# changer.net
KiCad netlist of a schematic drawn in EAGLE
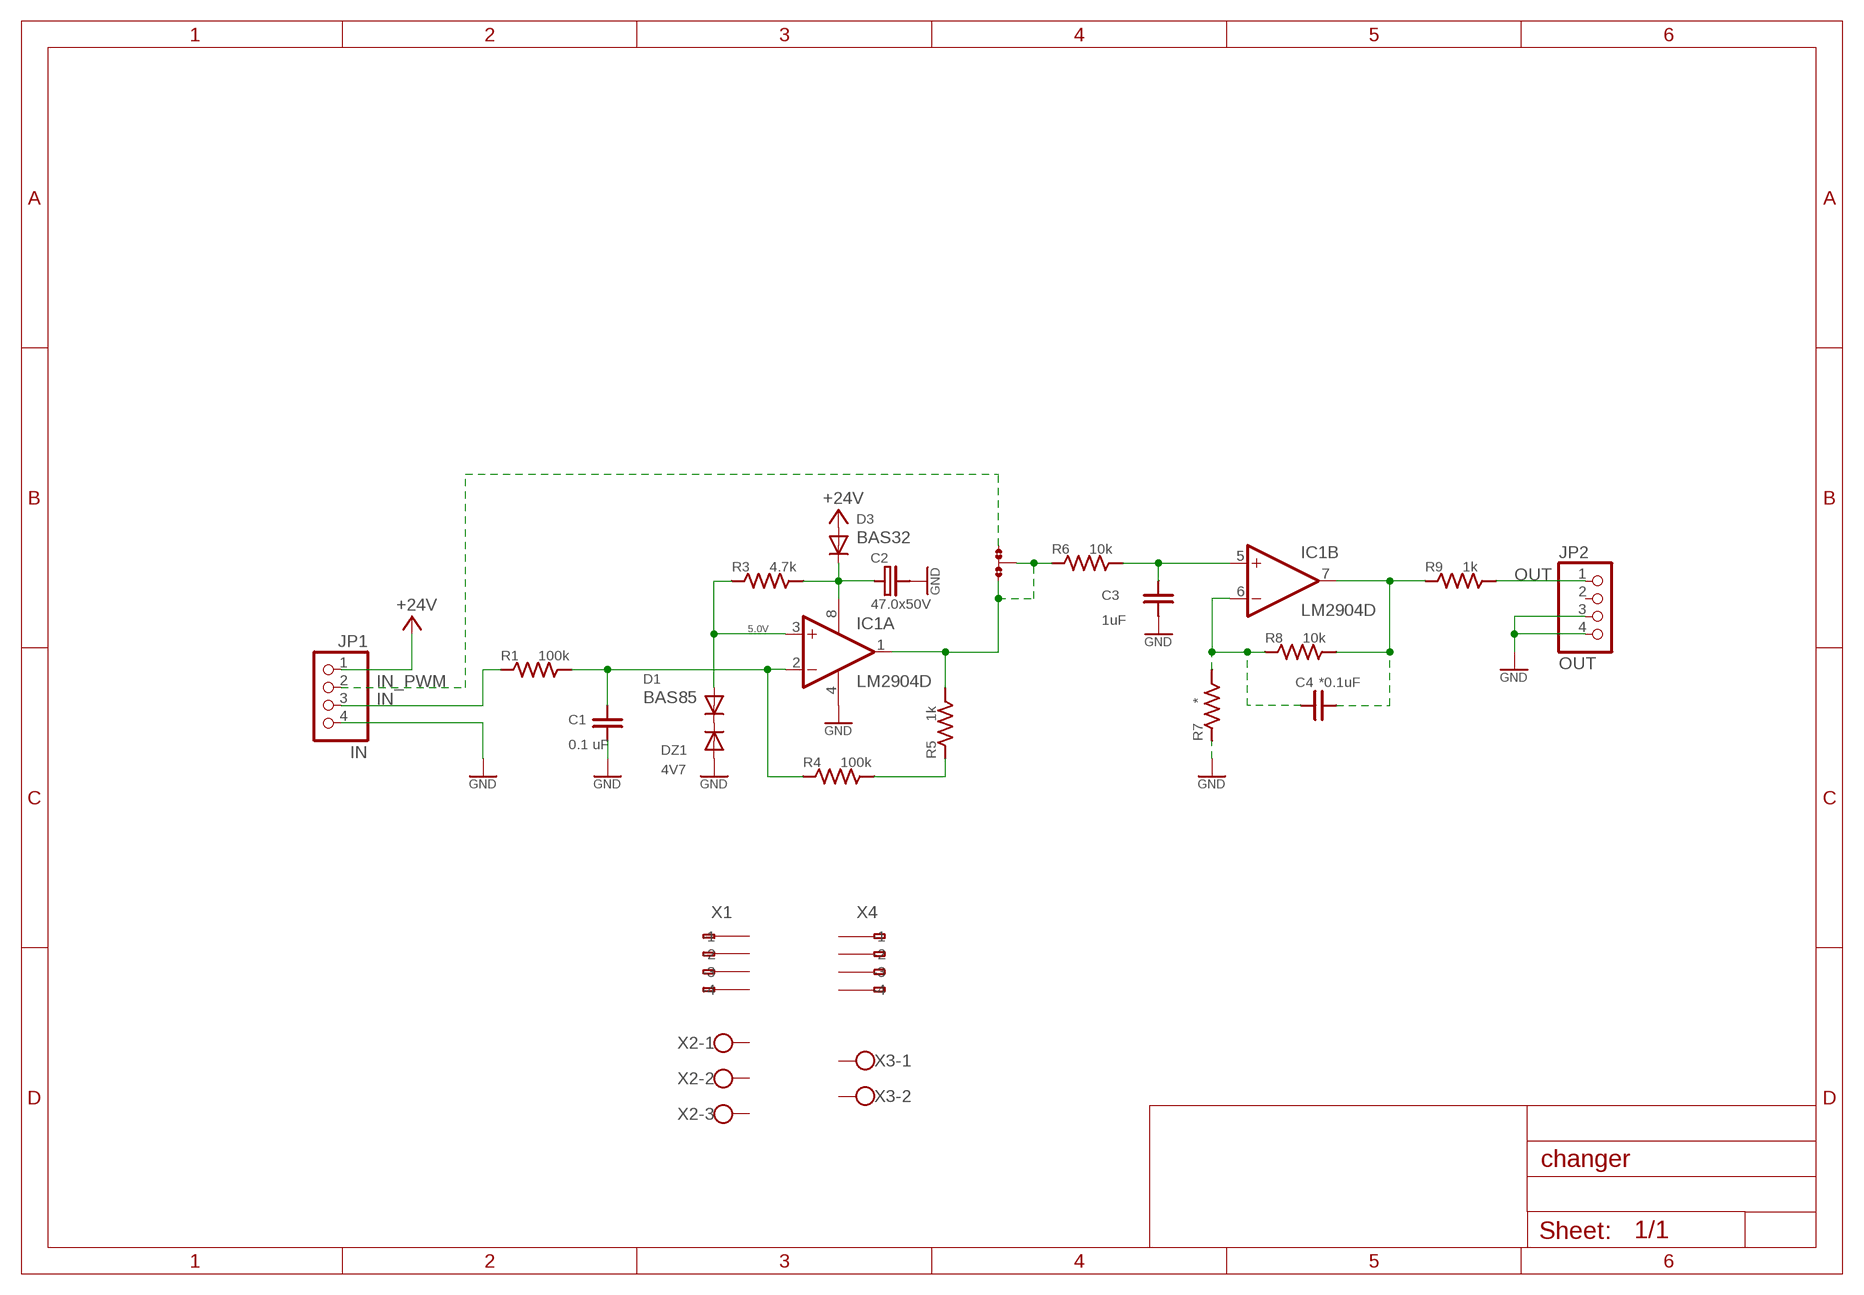
[diagram p0: schematic, sheet 1]

(export (version "E")
  (design (tool "Eeschema 10.0.6"))
  (components
    (comp (ref "C1")
      (value "0.1 uF")
      (footprint "eagle-import:C0805")
      (libsource (lib "eagle-import") (part "C/0805"))
    )
    (comp (ref "C2")
      (value "47.0x50V")
      (footprint "eagle-import:E2,5-5")
      (libsource (lib "eagle-import") (part "CPOL/E2,5-5"))
    )
    (comp (ref "C3")
      (value "1uF")
      (footprint "eagle-import:C0805")
      (libsource (lib "eagle-import") (part "C/0805"))
    )
    (comp (ref "C4")
      (value "*0.1uF")
      (footprint "eagle-import:C0805")
      (libsource (lib "eagle-import") (part "C/0805"))
    )
    (comp (ref "D1")
      (value "BAS85")
      (footprint "eagle-import:MINIMELF")
      (libsource (lib "eagle-import") (part "DIODE-MINIMELF"))
    )
    (comp (ref "D3")
      (value "BAS32")
      (footprint "eagle-import:MINIMELF")
      (libsource (lib "eagle-import") (part "DIODE-MINIMELF"))
    )
    (comp (ref "DZ1")
      (value "4V7")
      (footprint "eagle-import:MINIMELF")
      (libsource (lib "eagle-import") (part "DIODE-MINIMELF"))
    )
    (comp (ref "IC1")
      (value "LM2904D")
      (footprint "eagle-import:SO08")
      (libsource (lib "eagle-import") (part "LM2903D"))
    )
    (comp (ref "JMP1")
      (value "JUMP")
      (footprint "eagle-import:A0R-JMP")
      (libsource (lib "eagle-import") (part "0R-JUMPA"))
    )
    (comp (ref "JP1")
      (value "IN")
      (footprint "eagle-import:1X04")
      (libsource (lib "eagle-import") (part "PINHD-1X4"))
    )
    (comp (ref "JP2")
      (value "OUT")
      (footprint "eagle-import:1X04")
      (libsource (lib "eagle-import") (part "PINHD-1X4"))
    )
    (comp (ref "R1")
      (value "100k")
      (footprint "eagle-import:R0805")
      (libsource (lib "eagle-import") (part "R/0805"))
    )
    (comp (ref "R3")
      (value "4.7k")
      (footprint "eagle-import:R0805")
      (libsource (lib "eagle-import") (part "R/0805"))
    )
    (comp (ref "R4")
      (value "100k")
      (footprint "eagle-import:R0805")
      (libsource (lib "eagle-import") (part "R/0805"))
    )
    (comp (ref "R5")
      (value "1k")
      (footprint "eagle-import:R0805")
      (libsource (lib "eagle-import") (part "R/0805"))
    )
    (comp (ref "R6")
      (value "10k")
      (footprint "eagle-import:R0805")
      (libsource (lib "eagle-import") (part "R/0805"))
    )
    (comp (ref "R7")
      (value "*")
      (footprint "eagle-import:R0805")
      (libsource (lib "eagle-import") (part "R/0805"))
    )
    (comp (ref "R8")
      (value "10k")
      (footprint "eagle-import:R0805")
      (libsource (lib "eagle-import") (part "R/0805"))
    )
    (comp (ref "R9")
      (value "1k")
      (footprint "eagle-import:R0805")
      (libsource (lib "eagle-import") (part "R/0805"))
    )
    (comp (ref "X1")
      (value "233-104")
      (footprint "eagle-import:233-104")
      (libsource (lib "eagle-import") (part "233-104"))
    )
    (comp (ref "X2")
      (value "W237-103")
      (footprint "eagle-import:W237-103")
      (libsource (lib "eagle-import") (part "W237-103"))
    )
    (comp (ref "X3")
      (value "W237-102")
      (footprint "eagle-import:W237-102")
      (libsource (lib "eagle-import") (part "W237-102"))
    )
    (comp (ref "X4")
      (value "233-104")
      (footprint "eagle-import:233-104")
      (libsource (lib "eagle-import") (part "233-104"))
    )
  )
  (nets
    (net (code "1") (name "+24V") (class "Default")
      (node (ref "D3") (pin "A") (pinfunction "A_A") (pintype "passive"))
      (node (ref "JP1") (pin "1") (pinfunction "1_1") (pintype "passive"))
    )
    (net (code "2") (name "/IN") (class "Default")
      (node (ref "JP1") (pin "3") (pinfunction "3_3") (pintype "passive"))
      (node (ref "R1") (pin "1") (pinfunction "P$1_1") (pintype "bidirectional"))
    )
    (net (code "3") (name "/IN_PWM") (class "Default")
      (node (ref "JMP1") (pin "1") (pinfunction "1_1") (pintype "passive"))
      (node (ref "JP1") (pin "2") (pinfunction "2_2") (pintype "passive"))
    )
    (net (code "4") (name "/OUT") (class "Default")
      (node (ref "JP2") (pin "1") (pinfunction "1_1") (pintype "passive"))
      (node (ref "R9") (pin "2") (pinfunction "P$2_2") (pintype "bidirectional"))
    )
    (net (code "5") (name "GND") (class "Default")
      (node (ref "C1") (pin "1") (pinfunction "P$1_1") (pintype "bidirectional"))
      (node (ref "C2") (pin "-") (pinfunction "-_-") (pintype "bidirectional"))
      (node (ref "C3") (pin "1") (pinfunction "P$1_1") (pintype "bidirectional"))
      (node (ref "DZ1") (pin "A") (pinfunction "A_A") (pintype "passive"))
      (node (ref "IC1") (pin "4") (pinfunction "V-_4") (pintype "power_in"))
      (node (ref "JP1") (pin "4") (pinfunction "4_4") (pintype "passive"))
      (node (ref "JP2") (pin "3") (pinfunction "3_3") (pintype "passive"))
      (node (ref "JP2") (pin "4") (pinfunction "4_4") (pintype "passive"))
      (node (ref "R7") (pin "1") (pinfunction "P$1_1") (pintype "bidirectional"))
    )
    (net (code "6") (name "Net-(C1-P$2)") (class "Default")
      (node (ref "C1") (pin "2") (pinfunction "P$2_2") (pintype "bidirectional"))
      (node (ref "IC1") (pin "2") (pinfunction "-IN_2") (pintype "input"))
      (node (ref "R1") (pin "2") (pinfunction "P$2_2") (pintype "bidirectional"))
      (node (ref "R4") (pin "1") (pinfunction "P$1_1") (pintype "bidirectional"))
    )
    (net (code "7") (name "Net-(C3-P$2)") (class "Default")
      (node (ref "C3") (pin "2") (pinfunction "P$2_2") (pintype "bidirectional"))
      (node (ref "IC1") (pin "5") (pinfunction "+IN_5") (pintype "input"))
      (node (ref "R6") (pin "2") (pinfunction "P$2_2") (pintype "bidirectional"))
    )
    (net (code "8") (name "Net-(C4-P$1)") (class "Default")
      (node (ref "C4") (pin "1") (pinfunction "P$1_1") (pintype "bidirectional"))
      (node (ref "IC1") (pin "6") (pinfunction "-IN_6") (pintype "input"))
      (node (ref "R7") (pin "2") (pinfunction "P$2_2") (pintype "bidirectional"))
      (node (ref "R8") (pin "1") (pinfunction "P$1_1") (pintype "bidirectional"))
    )
    (net (code "9") (name "Net-(C4-P$2)") (class "Default")
      (node (ref "C4") (pin "2") (pinfunction "P$2_2") (pintype "bidirectional"))
      (node (ref "IC1") (pin "7") (pinfunction "OUT_7") (pintype "output"))
      (node (ref "R8") (pin "2") (pinfunction "P$2_2") (pintype "bidirectional"))
      (node (ref "R9") (pin "1") (pinfunction "P$1_1") (pintype "bidirectional"))
    )
    (net (code "10") (name "Net-(D1-PadC)") (class "Default")
      (node (ref "D1") (pin "C") (pinfunction "C_C") (pintype "passive"))
      (node (ref "DZ1") (pin "C") (pinfunction "C_C") (pintype "passive"))
    )
    (net (code "11") (name "Net-(IC1A-+IN)") (class "Default")
      (node (ref "D1") (pin "A") (pinfunction "A_A") (pintype "passive"))
      (node (ref "IC1") (pin "3") (pinfunction "+IN_3") (pintype "input"))
      (node (ref "R3") (pin "1") (pinfunction "P$1_1") (pintype "bidirectional"))
    )
    (net (code "12") (name "Net-(IC1A-OUT)") (class "Default")
      (node (ref "IC1") (pin "1") (pinfunction "OUT_1") (pintype "output"))
      (node (ref "JMP1") (pin "2") (pinfunction "2_2") (pintype "passive"))
      (node (ref "JMP1") (pin "3") (pinfunction "3_3") (pintype "passive"))
      (node (ref "R5") (pin "2") (pinfunction "P$2_2") (pintype "bidirectional"))
      (node (ref "R6") (pin "1") (pinfunction "P$1_1") (pintype "bidirectional"))
    )
    (net (code "13") (name "Net-(IC1C-V+)") (class "Default")
      (node (ref "C2") (pin "+") (pinfunction "+_+") (pintype "bidirectional"))
      (node (ref "D3") (pin "C") (pinfunction "C_C") (pintype "passive"))
      (node (ref "IC1") (pin "8") (pinfunction "V+_8") (pintype "power_in"))
      (node (ref "R3") (pin "2") (pinfunction "P$2_2") (pintype "bidirectional"))
    )
    (net (code "14") (name "Net-(R4-P$2)") (class "Default")
      (node (ref "R4") (pin "2") (pinfunction "P$2_2") (pintype "bidirectional"))
      (node (ref "R5") (pin "1") (pinfunction "P$1_1") (pintype "bidirectional"))
    )
    (net (code "15") (name "unconnected-(JP2-Pad2)") (class "Default")
      (node (ref "JP2") (pin "2") (pinfunction "2_2") (pintype "passive"))
    )
    (net (code "16") (name "unconnected-(X1--1-PadA1)") (class "Default")
      (node (ref "X1") (pin "A1") (pinfunction "-1_A1") (pintype "passive"))
    )
    (net (code "17") (name "unconnected-(X1--2-PadA2)") (class "Default")
      (node (ref "X1") (pin "A2") (pinfunction "-2_A2") (pintype "passive"))
    )
    (net (code "18") (name "unconnected-(X1--3-PadA3)") (class "Default")
      (node (ref "X1") (pin "A3") (pinfunction "-3_A3") (pintype "passive"))
    )
    (net (code "19") (name "unconnected-(X1--4-PadA4)") (class "Default")
      (node (ref "X1") (pin "A4") (pinfunction "-4_A4") (pintype "passive"))
    )
    (net (code "20") (name "unconnected-(X1-B-1-PadB1)") (class "Default")
      (node (ref "X1") (pin "B1") (pinfunction "B-1_B1") (pintype "passive"))
    )
    (net (code "21") (name "unconnected-(X1-B-2-PadB2)") (class "Default")
      (node (ref "X1") (pin "B2") (pinfunction "B-2_B2") (pintype "passive"))
    )
    (net (code "22") (name "unconnected-(X1-B-3-PadB3)") (class "Default")
      (node (ref "X1") (pin "B3") (pinfunction "B-3_B3") (pintype "passive"))
    )
    (net (code "23") (name "unconnected-(X1-B-4-PadB4)") (class "Default")
      (node (ref "X1") (pin "B4") (pinfunction "B-4_B4") (pintype "passive"))
    )
    (net (code "24") (name "unconnected-(X2A-KL-Pad1)") (class "Default")
      (node (ref "X2") (pin "1") (pinfunction "KL_1") (pintype "passive"))
    )
    (net (code "25") (name "unconnected-(X2B-KL-Pad2)") (class "Default")
      (node (ref "X2") (pin "2") (pinfunction "KL_2") (pintype "passive"))
    )
    (net (code "26") (name "unconnected-(X2C-KL-Pad3)") (class "Default")
      (node (ref "X2") (pin "3") (pinfunction "KL_3") (pintype "passive"))
    )
    (net (code "27") (name "unconnected-(X3A-KL-Pad1)") (class "Default")
      (node (ref "X3") (pin "1") (pinfunction "KL_1") (pintype "passive"))
    )
    (net (code "28") (name "unconnected-(X3B-KL-Pad2)") (class "Default")
      (node (ref "X3") (pin "2") (pinfunction "KL_2") (pintype "passive"))
    )
    (net (code "29") (name "unconnected-(X4--1-PadA1)") (class "Default")
      (node (ref "X4") (pin "A1") (pinfunction "-1_A1") (pintype "passive"))
    )
    (net (code "30") (name "unconnected-(X4--2-PadA2)") (class "Default")
      (node (ref "X4") (pin "A2") (pinfunction "-2_A2") (pintype "passive"))
    )
    (net (code "31") (name "unconnected-(X4--3-PadA3)") (class "Default")
      (node (ref "X4") (pin "A3") (pinfunction "-3_A3") (pintype "passive"))
    )
    (net (code "32") (name "unconnected-(X4--4-PadA4)") (class "Default")
      (node (ref "X4") (pin "A4") (pinfunction "-4_A4") (pintype "passive"))
    )
    (net (code "33") (name "unconnected-(X4-B-1-PadB1)") (class "Default")
      (node (ref "X4") (pin "B1") (pinfunction "B-1_B1") (pintype "passive"))
    )
    (net (code "34") (name "unconnected-(X4-B-2-PadB2)") (class "Default")
      (node (ref "X4") (pin "B2") (pinfunction "B-2_B2") (pintype "passive"))
    )
    (net (code "35") (name "unconnected-(X4-B-3-PadB3)") (class "Default")
      (node (ref "X4") (pin "B3") (pinfunction "B-3_B3") (pintype "passive"))
    )
    (net (code "36") (name "unconnected-(X4-B-4-PadB4)") (class "Default")
      (node (ref "X4") (pin "B4") (pinfunction "B-4_B4") (pintype "passive"))
    )
  )
)
